# P2H2-001.net
KiCad netlist of a schematic drawn in EAGLE
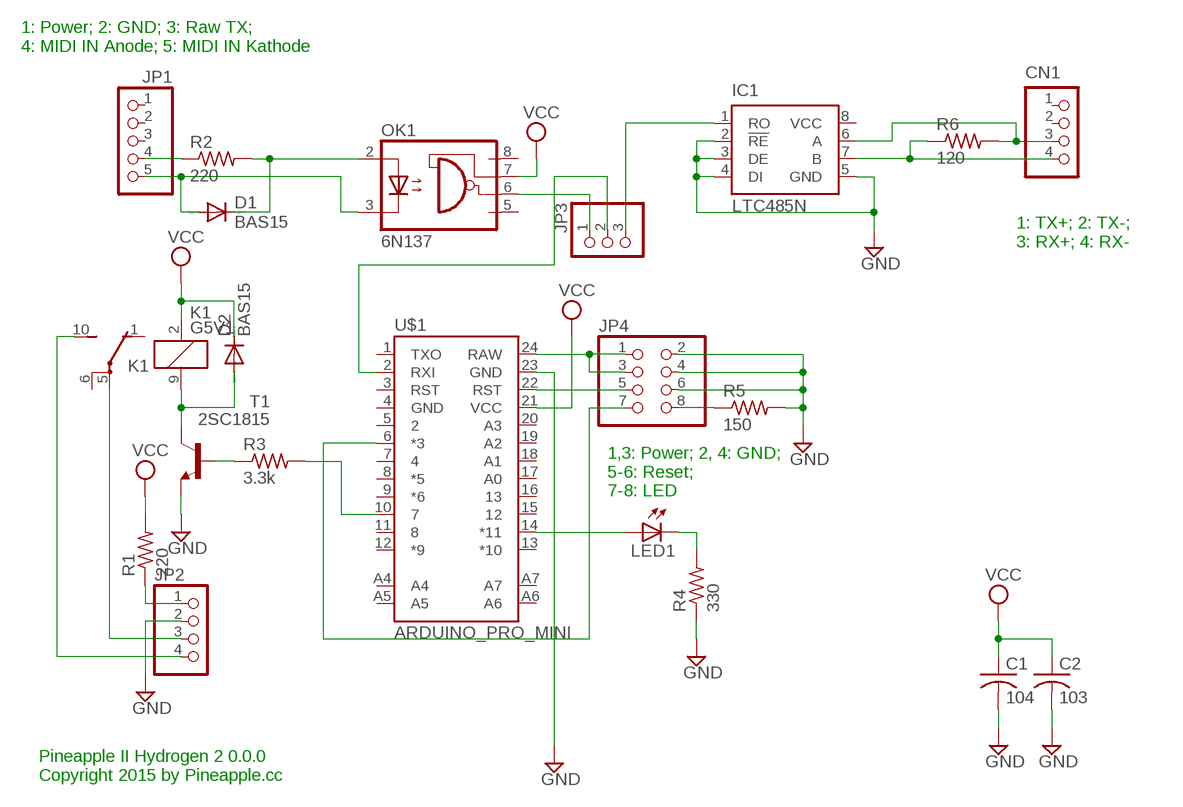
[diagram p0: schematic, sheet 1]

(export (version "E")
  (design (tool "Eeschema 10.0.6"))
  (components
    (comp (ref "C1")
      (value "104")
      (footprint "eagle-import:C025-025X050")
      (libsource (lib "eagle-import") (part "C-US025-025X050"))
    )
    (comp (ref "C2")
      (value "103")
      (footprint "eagle-import:C025-025X050")
      (libsource (lib "eagle-import") (part "C-US025-025X050"))
    )
    (comp (ref "CN1")
      (value "B4B-PH-K-S")
      (footprint "eagle-import:B4B-PH-K-S")
      (libsource (lib "eagle-import") (part "B4B-PH-K-S"))
    )
    (comp (ref "D1")
      (value "BAS15")
      (footprint "eagle-import:DO34-7")
      (libsource (lib "eagle-import") (part "BAS15"))
    )
    (comp (ref "D2")
      (value "BAS15")
      (footprint "eagle-import:DO34-7")
      (libsource (lib "eagle-import") (part "BAS15"))
    )
    (comp (ref "IC1")
      (value "LTC485N")
      (footprint "eagle-import:DIL08")
      (libsource (lib "eagle-import") (part "LTC485N"))
    )
    (comp (ref "JP1")
      (value "PINHD-1X5")
      (footprint "eagle-import:1X05")
      (libsource (lib "eagle-import") (part "PINHD-1X5"))
    )
    (comp (ref "JP2")
      (value "PINHD-1X4")
      (footprint "eagle-import:1X04")
      (libsource (lib "eagle-import") (part "PINHD-1X4"))
    )
    (comp (ref "JP3")
      (value "PINHD-1X3")
      (footprint "eagle-import:1X03")
      (libsource (lib "eagle-import") (part "PINHD-1X3"))
    )
    (comp (ref "JP4")
      (value "PINHD-2X4")
      (footprint "eagle-import:2X04")
      (libsource (lib "eagle-import") (part "PINHD-2X4"))
    )
    (comp (ref "K1")
      (value "G5V1")
      (footprint "eagle-import:G5V1")
      (fields (field (name "MPN") "G5V-1-DC24"))
      (libsource (lib "eagle-import") (part "G5V1"))
    )
    (comp (ref "LED1")
      (value "LED3MM")
      (footprint "eagle-import:LED3MM")
      (libsource (lib "eagle-import") (part "LED3MM"))
    )
    (comp (ref "OK1")
      (value "6N137")
      (footprint "eagle-import:DIL08")
      (libsource (lib "eagle-import") (part "6N137"))
    )
    (comp (ref "R1")
      (value "220")
      (footprint "eagle-import:0204_5")
      (libsource (lib "eagle-import") (part "R-US_0204/5"))
    )
    (comp (ref "R2")
      (value "220")
      (footprint "eagle-import:0204_5")
      (libsource (lib "eagle-import") (part "R-US_0204/5"))
    )
    (comp (ref "R3")
      (value "3.3k")
      (footprint "eagle-import:0204_5")
      (libsource (lib "eagle-import") (part "R-US_0204/5"))
    )
    (comp (ref "R4")
      (value "330")
      (footprint "eagle-import:0204_5")
      (libsource (lib "eagle-import") (part "R-US_0204/5"))
    )
    (comp (ref "R5")
      (value "150")
      (footprint "eagle-import:0204_5")
      (libsource (lib "eagle-import") (part "R-US_0204/5"))
    )
    (comp (ref "R6")
      (value "120")
      (footprint "eagle-import:0204_5")
      (libsource (lib "eagle-import") (part "R-US_0204/5"))
    )
    (comp (ref "T1")
      (value "2SC1815")
      (footprint "eagle-import:TO92-ECB")
      (libsource (lib "eagle-import") (part "2SC1815"))
    )
    (comp (ref "U$1")
      (value "ARDUINO_PRO_MINI")
      (footprint "eagle-import:ARDUINO_PRO_MINI")
      (libsource (lib "eagle-import") (part "ARDUINO_PRO_MINI"))
    )
  )
  (nets
    (net (code "1") (name "GND") (class "Default")
      (node (ref "C1") (pin "2") (pinfunction "2_2") (pintype "passive"))
      (node (ref "C2") (pin "2") (pinfunction "2_2") (pintype "passive"))
      (node (ref "IC1") (pin "2") (pinfunction "~{RE}_2") (pintype "input"))
      (node (ref "IC1") (pin "3") (pinfunction "DE_3") (pintype "input"))
      (node (ref "IC1") (pin "4") (pinfunction "DI_4") (pintype "input"))
      (node (ref "IC1") (pin "5") (pinfunction "GND_5") (pintype "input"))
      (node (ref "JP2") (pin "2") (pinfunction "2_2") (pintype "passive"))
      (node (ref "JP4") (pin "2") (pinfunction "2_2") (pintype "passive"))
      (node (ref "JP4") (pin "4") (pinfunction "4_4") (pintype "passive"))
      (node (ref "JP4") (pin "6") (pinfunction "6_6") (pintype "passive"))
      (node (ref "R4") (pin "1") (pinfunction "1_1") (pintype "passive"))
      (node (ref "R5") (pin "2") (pinfunction "2_2") (pintype "passive"))
      (node (ref "T1") (pin "E") (pinfunction "E_E") (pintype "passive"))
      (node (ref "U$1") (pin "23") (pinfunction "GND_23") (pintype "bidirectional"))
    )
    (net (code "2") (name "Net-(IC1-A)") (class "Default")
      (node (ref "CN1") (pin "3") (pinfunction "3_3") (pintype "passive"))
      (node (ref "IC1") (pin "6") (pinfunction "A_6") (pintype "bidirectional"))
      (node (ref "R6") (pin "2") (pinfunction "2_2") (pintype "passive"))
    )
    (net (code "3") (name "Net-(IC1-B)") (class "Default")
      (node (ref "CN1") (pin "4") (pinfunction "4_4") (pintype "passive"))
      (node (ref "IC1") (pin "7") (pinfunction "B_7") (pintype "bidirectional"))
      (node (ref "R6") (pin "1") (pinfunction "1_1") (pintype "passive"))
    )
    (net (code "4") (name "Net-(IC1-RO)") (class "Default")
      (node (ref "IC1") (pin "1") (pinfunction "RO_1") (pintype "output"))
      (node (ref "JP3") (pin "3") (pinfunction "3_3") (pintype "passive"))
    )
    (net (code "5") (name "Net-(JP1-Pad4)") (class "Default")
      (node (ref "JP1") (pin "4") (pinfunction "4_4") (pintype "passive"))
      (node (ref "R2") (pin "1") (pinfunction "1_1") (pintype "passive"))
    )
    (net (code "6") (name "Net-(JP2-Pad1)") (class "Default")
      (node (ref "JP2") (pin "1") (pinfunction "1_1") (pintype "passive"))
      (node (ref "R1") (pin "1") (pinfunction "1_1") (pintype "passive"))
    )
    (net (code "7") (name "Net-(JP2-Pad3)") (class "Default")
      (node (ref "JP2") (pin "3") (pinfunction "3_3") (pintype "passive"))
      (node (ref "K1") (pin "5") (pinfunction "P_5") (pintype "passive"))
    )
    (net (code "8") (name "Net-(JP4-Pad5)") (class "Default")
      (node (ref "JP4") (pin "5") (pinfunction "5_5") (pintype "passive"))
      (node (ref "U$1") (pin "22") (pinfunction "RST_22") (pintype "bidirectional"))
    )
    (net (code "9") (name "Net-(JP4-Pad8)") (class "Default")
      (node (ref "JP4") (pin "8") (pinfunction "8_8") (pintype "passive"))
      (node (ref "R5") (pin "1") (pinfunction "1_1") (pintype "passive"))
    )
    (net (code "10") (name "Net-(K1A-2)") (class "Default")
      (node (ref "D2") (pin "A") (pinfunction "A_A") (pintype "passive"))
      (node (ref "K1") (pin "9") (pinfunction "2_9") (pintype "passive"))
      (node (ref "T1") (pin "C") (pinfunction "C_C") (pintype "passive"))
    )
    (net (code "11") (name "Net-(K1B-S)") (class "Default")
      (node (ref "JP2") (pin "4") (pinfunction "4_4") (pintype "passive"))
      (node (ref "K1") (pin "10") (pinfunction "S_10") (pintype "passive"))
    )
    (net (code "12") (name "Net-(LED1-C)") (class "Default")
      (node (ref "LED1") (pin "K") (pinfunction "C_K") (pintype "passive"))
      (node (ref "R4") (pin "2") (pinfunction "2_2") (pintype "passive"))
    )
    (net (code "13") (name "Net-(OK1-A)") (class "Default")
      (node (ref "D1") (pin "C") (pinfunction "C_C") (pintype "passive"))
      (node (ref "OK1") (pin "2") (pinfunction "A_2") (pintype "passive"))
      (node (ref "R2") (pin "2") (pinfunction "2_2") (pintype "passive"))
    )
    (net (code "14") (name "Net-(OK1-C)") (class "Default")
      (node (ref "D1") (pin "A") (pinfunction "A_A") (pintype "passive"))
      (node (ref "JP1") (pin "5") (pinfunction "5_5") (pintype "passive"))
      (node (ref "OK1") (pin "3") (pinfunction "C_3") (pintype "passive"))
    )
    (net (code "15") (name "Net-(OK1-VO)") (class "Default")
      (node (ref "JP3") (pin "1") (pinfunction "1_1") (pintype "passive"))
      (node (ref "OK1") (pin "6") (pinfunction "VO_6") (pintype "passive"))
    )
    (net (code "16") (name "Net-(R3-Pad1)") (class "Default")
      (node (ref "R3") (pin "1") (pinfunction "1_1") (pintype "passive"))
      (node (ref "T1") (pin "B") (pinfunction "B_B") (pintype "passive"))
    )
    (net (code "17") (name "Net-(U$1-*3)") (class "Default")
      (node (ref "JP4") (pin "7") (pinfunction "7_7") (pintype "passive"))
      (node (ref "U$1") (pin "6") (pinfunction "*3_6") (pintype "bidirectional"))
    )
    (net (code "18") (name "Net-(U$1-*11)") (class "Default")
      (node (ref "LED1") (pin "A") (pinfunction "A_A") (pintype "passive"))
      (node (ref "U$1") (pin "14") (pinfunction "*11_14") (pintype "bidirectional"))
    )
    (net (code "19") (name "Net-(U$1-7)") (class "Default")
      (node (ref "R3") (pin "2") (pinfunction "2_2") (pintype "passive"))
      (node (ref "U$1") (pin "10") (pinfunction "7_10") (pintype "bidirectional"))
    )
    (net (code "20") (name "Net-(U$1-RAW)") (class "Default")
      (node (ref "JP4") (pin "1") (pinfunction "1_1") (pintype "passive"))
      (node (ref "JP4") (pin "3") (pinfunction "3_3") (pintype "passive"))
      (node (ref "U$1") (pin "24") (pinfunction "RAW_24") (pintype "bidirectional"))
    )
    (net (code "21") (name "Net-(U$1-RXI)") (class "Default")
      (node (ref "JP3") (pin "2") (pinfunction "2_2") (pintype "passive"))
      (node (ref "U$1") (pin "2") (pinfunction "RXI_2") (pintype "bidirectional"))
    )
    (net (code "22") (name "VCC") (class "Default")
      (node (ref "C1") (pin "1") (pinfunction "1_1") (pintype "passive"))
      (node (ref "C2") (pin "1") (pinfunction "1_1") (pintype "passive"))
      (node (ref "D2") (pin "C") (pinfunction "C_C") (pintype "passive"))
      (node (ref "K1") (pin "2") (pinfunction "1_2") (pintype "passive"))
      (node (ref "OK1") (pin "7") (pinfunction "VE_7") (pintype "passive"))
      (node (ref "R1") (pin "2") (pinfunction "2_2") (pintype "passive"))
      (node (ref "U$1") (pin "21") (pinfunction "VCC_21") (pintype "bidirectional"))
    )
    (net (code "23") (name "unconnected-(CN1-Pad1)") (class "Default")
      (node (ref "CN1") (pin "1") (pinfunction "1_1") (pintype "passive"))
    )
    (net (code "24") (name "unconnected-(CN1-Pad2)") (class "Default")
      (node (ref "CN1") (pin "2") (pinfunction "2_2") (pintype "passive"))
    )
    (net (code "25") (name "unconnected-(IC1-VCC-Pad8)") (class "Default")
      (node (ref "IC1") (pin "8") (pinfunction "VCC_8") (pintype "input"))
    )
    (net (code "26") (name "unconnected-(JP1-Pad1)") (class "Default")
      (node (ref "JP1") (pin "1") (pinfunction "1_1") (pintype "passive"))
    )
    (net (code "27") (name "unconnected-(JP1-Pad2)") (class "Default")
      (node (ref "JP1") (pin "2") (pinfunction "2_2") (pintype "passive"))
    )
    (net (code "28") (name "unconnected-(JP1-Pad3)") (class "Default")
      (node (ref "JP1") (pin "3") (pinfunction "3_3") (pintype "passive"))
    )
    (net (code "29") (name "unconnected-(K1B-O-Pad1)") (class "Default")
      (node (ref "K1") (pin "1") (pinfunction "O_1") (pintype "passive"))
    )
    (net (code "30") (name "unconnected-(K1B-P-Pad6)") (class "Default")
      (node (ref "K1") (pin "6") (pinfunction "P_6") (pintype "passive"))
    )
    (net (code "31") (name "unconnected-(OK1-GND-Pad5)") (class "Default")
      (node (ref "OK1") (pin "5") (pinfunction "GND_5") (pintype "passive"))
    )
    (net (code "32") (name "unconnected-(OK1-VCC-Pad8)") (class "Default")
      (node (ref "OK1") (pin "8") (pinfunction "VCC_8") (pintype "passive"))
    )
    (net (code "33") (name "unconnected-(U$1-*5-Pad8)") (class "Default")
      (node (ref "U$1") (pin "8") (pinfunction "*5_8") (pintype "bidirectional"))
    )
    (net (code "34") (name "unconnected-(U$1-*6-Pad9)") (class "Default")
      (node (ref "U$1") (pin "9") (pinfunction "*6_9") (pintype "bidirectional"))
    )
    (net (code "35") (name "unconnected-(U$1-*9-Pad12)") (class "Default")
      (node (ref "U$1") (pin "12") (pinfunction "*9_12") (pintype "bidirectional"))
    )
    (net (code "36") (name "unconnected-(U$1-*10-Pad13)") (class "Default")
      (node (ref "U$1") (pin "13") (pinfunction "*10_13") (pintype "bidirectional"))
    )
    (net (code "37") (name "unconnected-(U$1-2-Pad5)") (class "Default")
      (node (ref "U$1") (pin "5") (pinfunction "2_5") (pintype "bidirectional"))
    )
    (net (code "38") (name "unconnected-(U$1-4-Pad7)") (class "Default")
      (node (ref "U$1") (pin "7") (pinfunction "4_7") (pintype "bidirectional"))
    )
    (net (code "39") (name "unconnected-(U$1-8-Pad11)") (class "Default")
      (node (ref "U$1") (pin "11") (pinfunction "8_11") (pintype "bidirectional"))
    )
    (net (code "40") (name "unconnected-(U$1-12-Pad15)") (class "Default")
      (node (ref "U$1") (pin "15") (pinfunction "12_15") (pintype "bidirectional"))
    )
    (net (code "41") (name "unconnected-(U$1-13-Pad16)") (class "Default")
      (node (ref "U$1") (pin "16") (pinfunction "13_16") (pintype "bidirectional"))
    )
    (net (code "42") (name "unconnected-(U$1-A0-Pad17)") (class "Default")
      (node (ref "U$1") (pin "17") (pinfunction "A0_17") (pintype "bidirectional"))
    )
    (net (code "43") (name "unconnected-(U$1-A1-Pad18)") (class "Default")
      (node (ref "U$1") (pin "18") (pinfunction "A1_18") (pintype "bidirectional"))
    )
    (net (code "44") (name "unconnected-(U$1-A2-Pad19)") (class "Default")
      (node (ref "U$1") (pin "19") (pinfunction "A2_19") (pintype "bidirectional"))
    )
    (net (code "45") (name "unconnected-(U$1-A3-Pad20)") (class "Default")
      (node (ref "U$1") (pin "20") (pinfunction "A3_20") (pintype "bidirectional"))
    )
    (net (code "46") (name "unconnected-(U$1-GND-Pad4)") (class "Default")
      (node (ref "U$1") (pin "4") (pinfunction "GND_4") (pintype "bidirectional"))
    )
    (net (code "47") (name "unconnected-(U$1-PadA4)") (class "Default")
      (node (ref "U$1") (pin "A4") (pinfunction "A4_A4") (pintype "bidirectional"))
    )
    (net (code "48") (name "unconnected-(U$1-PadA5)") (class "Default")
      (node (ref "U$1") (pin "A5") (pinfunction "A5_A5") (pintype "bidirectional"))
    )
    (net (code "49") (name "unconnected-(U$1-PadA6)") (class "Default")
      (node (ref "U$1") (pin "A6") (pinfunction "A6_A6") (pintype "bidirectional"))
    )
    (net (code "50") (name "unconnected-(U$1-PadA7)") (class "Default")
      (node (ref "U$1") (pin "A7") (pinfunction "A7_A7") (pintype "bidirectional"))
    )
    (net (code "51") (name "unconnected-(U$1-RST-Pad3)") (class "Default")
      (node (ref "U$1") (pin "3") (pinfunction "RST_3") (pintype "bidirectional"))
    )
    (net (code "52") (name "unconnected-(U$1-TXO-Pad1)") (class "Default")
      (node (ref "U$1") (pin "1") (pinfunction "TXO_1") (pintype "bidirectional"))
    )
  )
)
